# Main.net
KiCad netlist of a schematic drawn in Altium Designer
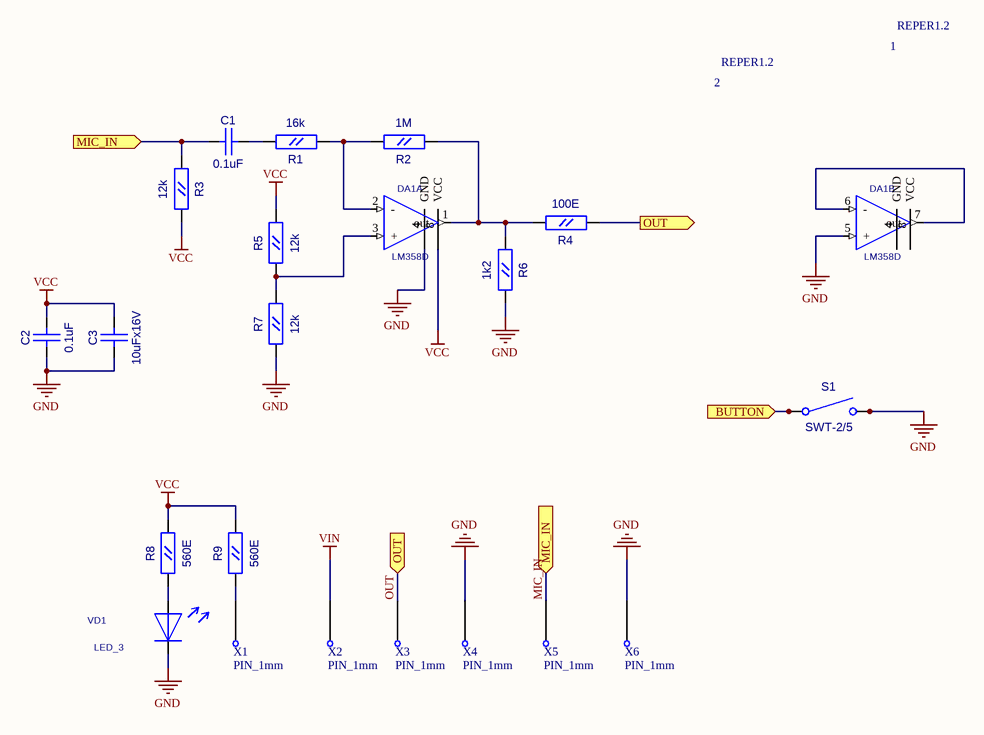
[diagram p0: Main.SchDoc]

(export (version "E")
  (design (tool "Eeschema 10.0.6"))
  (components
    (comp (ref "1")
      (value "REPER1.2")
      (footprint "REPER1.2")
      (libsource (lib "gprs_modem_2") (part "REPER1.2"))
    )
    (comp (ref "2")
      (value "REPER1.2")
      (footprint "REPER1.2")
      (libsource (lib "gprs_modem_2") (part "REPER1.2"))
    )
    (comp (ref "C1")
      (value "0.1uF")
      (footprint "CC0805")
      (description "CC0805")
      (libsource (lib "gprs_modem_2") (part "CC0805"))
    )
    (comp (ref "C2")
      (value "0.1uF")
      (footprint "CC0805")
      (description "CC0805")
      (libsource (lib "gprs_modem_2") (part "CC0805"))
    )
    (comp (ref "C3")
      (value "10uFx16V")
      (footprint "CC0805")
      (description "CC0805")
      (libsource (lib "gprs_modem_2") (part "CC0805"))
    )
    (comp (ref "DA1") (value "LM358D") (footprint "SO-8") (libsource (lib "Schetchik") (part "LM358D")))
    (comp (ref "R1")
      (value "16k")
      (footprint "RC0805")
      (description "RC0805")
      (libsource (lib "gprs_modem_2") (part "RC0805"))
    )
    (comp (ref "R2")
      (value "1M")
      (footprint "RC0805")
      (description "RC0805")
      (libsource (lib "gprs_modem_2") (part "RC0805"))
    )
    (comp (ref "R3")
      (value "12k")
      (footprint "RC0805")
      (description "RC0805")
      (libsource (lib "gprs_modem_2") (part "RC0805"))
    )
    (comp (ref "R4")
      (value "100E")
      (footprint "RC0805")
      (description "RC0805")
      (libsource (lib "gprs_modem_2") (part "RC0805"))
    )
    (comp (ref "R5")
      (value "12k")
      (footprint "RC0805")
      (description "RC0805")
      (libsource (lib "gprs_modem_2") (part "RC0805"))
    )
    (comp (ref "R6")
      (value "1k2")
      (footprint "RC0805")
      (description "RC0805")
      (libsource (lib "gprs_modem_2") (part "RC0805"))
    )
    (comp (ref "R7")
      (value "12k")
      (footprint "RC0805")
      (description "RC0805")
      (libsource (lib "gprs_modem_2") (part "RC0805"))
    )
    (comp (ref "R8")
      (value "560E")
      (footprint "RC0805")
      (description "RC0805")
      (libsource (lib "gprs_modem_2") (part "RC0805"))
    )
    (comp (ref "R9")
      (value "560E")
      (footprint "RC0805")
      (description "RC0805")
      (libsource (lib "gprs_modem_2") (part "RC0805"))
    )
    (comp (ref "S1")
      (value "SWT-2/5")
      (footprint "7906H-1")
      (description "Switch, Single Pole, Single Throw, Normally Open")
      (libsource (lib "gprs_modem_2") (part "SWT-2/5"))
    )
    (comp (ref "VD1") (value "LED_3") (footprint "LED3") (libsource (lib "gprs_modem_2") (part "LED_3")))
    (comp (ref "X1")
      (value "PIN_1mm")
      (footprint "PIN_1mm")
      (libsource (lib "gprs_modem_2") (part "PIN_1mm"))
    )
    (comp (ref "X2")
      (value "PIN_1mm")
      (footprint "PIN_1mm")
      (libsource (lib "gprs_modem_2") (part "PIN_1mm"))
    )
    (comp (ref "X3")
      (value "PIN_1mm")
      (footprint "PIN_1mm")
      (libsource (lib "gprs_modem_2") (part "PIN_1mm"))
    )
    (comp (ref "X4")
      (value "PIN_1mm")
      (footprint "PIN_1mm")
      (libsource (lib "gprs_modem_2") (part "PIN_1mm"))
    )
    (comp (ref "X5")
      (value "PIN_1mm")
      (footprint "PIN_1mm")
      (libsource (lib "gprs_modem_2") (part "PIN_1mm"))
    )
    (comp (ref "X6")
      (value "PIN_1mm")
      (footprint "PIN_1mm")
      (libsource (lib "gprs_modem_2") (part "PIN_1mm"))
    )
  )
  (nets
    (net (code "1") (name "/BUTTON") (class "Default")
      (node (ref "S1") (pin "1") (pinfunction "C1_1") (pintype "passive"))
      (node (ref "S1") (pin "2") (pintype "passive"))
    )
    (net (code "2") (name "/MIC_IN") (class "Default")
      (node (ref "C1") (pin "1") (pinfunction "A_1") (pintype "passive"))
      (node (ref "R3") (pin "1") (pinfunction "A_1") (pintype "passive"))
      (node (ref "X5") (pin "1") (pinfunction "1_1") (pintype "passive"))
    )
    (net (code "3") (name "/OUT") (class "Default")
      (node (ref "R4") (pin "1") (pinfunction "A_1") (pintype "passive"))
      (node (ref "X3") (pin "1") (pinfunction "1_1") (pintype "passive"))
    )
    (net (code "4") (name "GND") (class "Default")
      (node (ref "C2") (pin "1") (pinfunction "A_1") (pintype "passive"))
      (node (ref "C3") (pin "1") (pinfunction "A_1") (pintype "passive"))
      (node (ref "DA1") (pin "4") (pinfunction "GND_4") (pintype "power_in"))
      (node (ref "DA1") (pin "5") (pinfunction "+_5") (pintype "input"))
      (node (ref "R6") (pin "2") (pinfunction "B_2") (pintype "passive"))
      (node (ref "R7") (pin "1") (pinfunction "A_1") (pintype "passive"))
      (node (ref "S1") (pin "3") (pinfunction "C2_3") (pintype "passive"))
      (node (ref "S1") (pin "4") (pintype "passive"))
      (node (ref "VD1") (pin "1") (pintype "passive"))
      (node (ref "X4") (pin "1") (pinfunction "1_1") (pintype "passive"))
      (node (ref "X6") (pin "1") (pinfunction "1_1") (pintype "passive"))
    )
    (net (code "5") (name "Net-(C1-B)") (class "Default")
      (node (ref "C1") (pin "2") (pinfunction "B_2") (pintype "passive"))
      (node (ref "R1") (pin "2") (pinfunction "B_2") (pintype "passive"))
    )
    (net (code "6") (name "Net-(DA1A-+)") (class "Default")
      (node (ref "DA1") (pin "3") (pinfunction "+_3") (pintype "input"))
      (node (ref "R5") (pin "1") (pinfunction "A_1") (pintype "passive"))
      (node (ref "R7") (pin "2") (pinfunction "B_2") (pintype "passive"))
    )
    (net (code "7") (name "Net-(DA1A--)") (class "Default")
      (node (ref "DA1") (pin "2") (pinfunction "-_2") (pintype "input"))
      (node (ref "R1") (pin "1") (pinfunction "A_1") (pintype "passive"))
      (node (ref "R2") (pin "2") (pinfunction "B_2") (pintype "passive"))
    )
    (net (code "8") (name "Net-(DA1A-out)") (class "Default")
      (node (ref "DA1") (pin "1") (pinfunction "out_1") (pintype "output"))
      (node (ref "R2") (pin "1") (pinfunction "A_1") (pintype "passive"))
      (node (ref "R4") (pin "2") (pinfunction "B_2") (pintype "passive"))
      (node (ref "R6") (pin "1") (pinfunction "A_1") (pintype "passive"))
    )
    (net (code "9") (name "Net-(DA1B--)") (class "Default")
      (node (ref "DA1") (pin "6") (pinfunction "-_6") (pintype "input"))
      (node (ref "DA1") (pin "7") (pinfunction "out_7") (pintype "output"))
    )
    (net (code "10") (name "Net-(R8-A)") (class "Default")
      (node (ref "R8") (pin "1") (pinfunction "A_1") (pintype "passive"))
      (node (ref "VD1") (pin "2") (pintype "passive"))
    )
    (net (code "11") (name "Net-(R9-A)") (class "Default")
      (node (ref "R9") (pin "1") (pinfunction "A_1") (pintype "passive"))
      (node (ref "X1") (pin "1") (pinfunction "1_1") (pintype "passive"))
    )
    (net (code "12") (name "VCC") (class "Default")
      (node (ref "C2") (pin "2") (pinfunction "B_2") (pintype "passive"))
      (node (ref "C3") (pin "2") (pinfunction "B_2") (pintype "passive"))
      (node (ref "DA1") (pin "8") (pinfunction "VCC_8") (pintype "power_in"))
      (node (ref "R3") (pin "2") (pinfunction "B_2") (pintype "passive"))
      (node (ref "R5") (pin "2") (pinfunction "B_2") (pintype "passive"))
      (node (ref "R8") (pin "2") (pinfunction "B_2") (pintype "passive"))
      (node (ref "R9") (pin "2") (pinfunction "B_2") (pintype "passive"))
    )
    (net (code "13") (name "VIN") (class "Default")
      (node (ref "X2") (pin "1") (pinfunction "1_1") (pintype "passive"))
    )
    (net (code "14") (name "unconnected-(1-Pad1)") (class "Default")
      (node (ref "1") (pin "1") (pintype "passive"))
    )
    (net (code "15") (name "unconnected-(2-Pad1)") (class "Default")
      (node (ref "2") (pin "1") (pintype "passive"))
    )
  )
)
